# i2csensor.net
KiCad netlist of a schematic drawn in Altium Designer
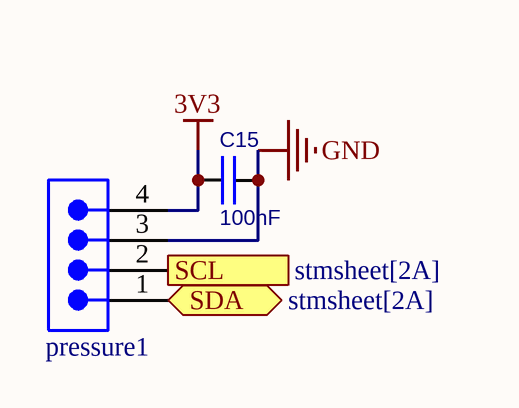
[diagram p0: i2csensor.SchDoc]

(export (version "E")
  (design (tool "Eeschema 10.0.6"))
  (components
    (comp (ref "C15")
      (value "100nF")
      (footprint "C0603")
      (description "Capacitor")
      (libsource (lib "General") (part "C"))
    )
    (comp (ref "pressure1")
      (value "COM&Heart")
      (footprint "691321100004")
      (fields (field (name "VOLTAGE") "300V"))
      (libsource (lib "Altium Content Vault") (part "TBL - 1R - 04P - Male"))
    )
  )
  (nets
    (net (code "1") (name "/SCL") (class "Default")
      (node (ref "pressure1") (pin "2") (pinfunction "2_2") (pintype "passive"))
    )
    (net (code "2") (name "/SDA") (class "Default")
      (node (ref "pressure1") (pin "1") (pinfunction "1_1") (pintype "passive"))
    )
    (net (code "3") (name "3V3") (class "Default")
      (node (ref "C15") (pin "1") (pinfunction "1_1") (pintype "passive"))
      (node (ref "pressure1") (pin "4") (pinfunction "4_4") (pintype "passive"))
    )
    (net (code "4") (name "GND") (class "Default")
      (node (ref "C15") (pin "2") (pinfunction "2_2") (pintype "passive"))
      (node (ref "pressure1") (pin "3") (pinfunction "3_3") (pintype "passive"))
    )
  )
)
